# SensorModuleConector.net
KiCad netlist of a schematic drawn in EAGLE
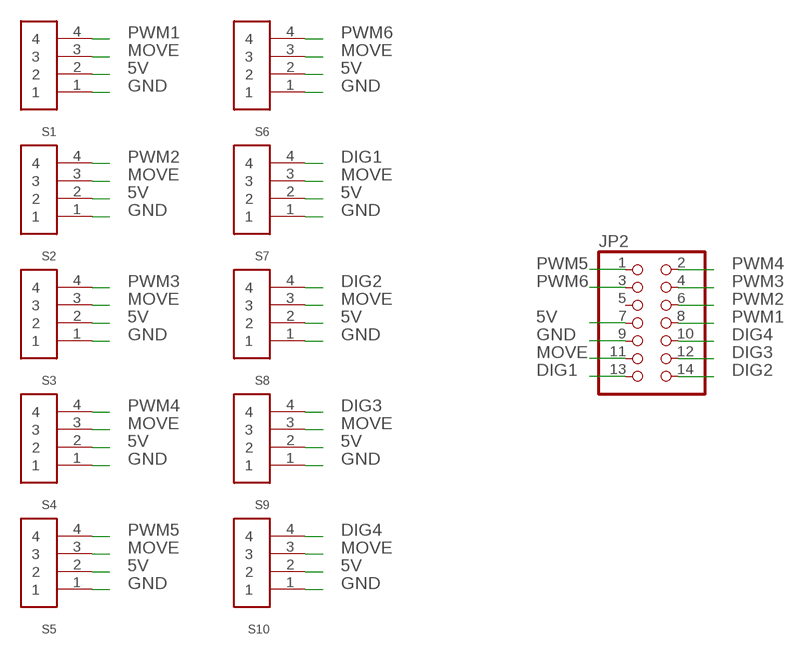
[diagram p0: schematic, sheet 1]

(export (version "E")
  (design (tool "Eeschema 10.0.6"))
  (components
    (comp (ref "JP2")
      (value "PINHD-2X7")
      (footprint "eagle-import:2X07")
      (libsource (lib "eagle-import") (part "PINHD-2X7"))
    )
    (comp (ref "S1")
      (value "CP150_1X4")
      (footprint "eagle-import:CP150_1X4")
      (libsource (lib "eagle-import") (part "CP150_1X4"))
    )
    (comp (ref "S2")
      (value "CP150_1X4")
      (footprint "eagle-import:CP150_1X4")
      (libsource (lib "eagle-import") (part "CP150_1X4"))
    )
    (comp (ref "S3")
      (value "CP150_1X4")
      (footprint "eagle-import:CP150_1X4")
      (libsource (lib "eagle-import") (part "CP150_1X4"))
    )
    (comp (ref "S4")
      (value "CP150_1X4")
      (footprint "eagle-import:CP150_1X4")
      (libsource (lib "eagle-import") (part "CP150_1X4"))
    )
    (comp (ref "S5")
      (value "CP150_1X4")
      (footprint "eagle-import:CP150_1X4")
      (libsource (lib "eagle-import") (part "CP150_1X4"))
    )
    (comp (ref "S6")
      (value "CP150_1X4")
      (footprint "eagle-import:CP150_1X4")
      (libsource (lib "eagle-import") (part "CP150_1X4"))
    )
    (comp (ref "S7")
      (value "CP150_1X4")
      (footprint "eagle-import:CP150_1X4")
      (libsource (lib "eagle-import") (part "CP150_1X4"))
    )
    (comp (ref "S8")
      (value "CP150_1X4")
      (footprint "eagle-import:CP150_1X4")
      (libsource (lib "eagle-import") (part "CP150_1X4"))
    )
    (comp (ref "S9")
      (value "CP150_1X4")
      (footprint "eagle-import:CP150_1X4")
      (libsource (lib "eagle-import") (part "CP150_1X4"))
    )
    (comp (ref "S10")
      (value "CP150_1X4")
      (footprint "eagle-import:CP150_1X4")
      (libsource (lib "eagle-import") (part "CP150_1X4"))
    )
  )
  (nets
    (net (code "1") (name "/5V") (class "Default")
      (node (ref "JP2") (pin "7") (pinfunction "7_7") (pintype "passive"))
      (node (ref "S1") (pin "2") (pinfunction "2_2") (pintype "bidirectional"))
      (node (ref "S10") (pin "2") (pinfunction "2_2") (pintype "bidirectional"))
      (node (ref "S2") (pin "2") (pinfunction "2_2") (pintype "bidirectional"))
      (node (ref "S3") (pin "2") (pinfunction "2_2") (pintype "bidirectional"))
      (node (ref "S4") (pin "2") (pinfunction "2_2") (pintype "bidirectional"))
      (node (ref "S5") (pin "2") (pinfunction "2_2") (pintype "bidirectional"))
      (node (ref "S6") (pin "2") (pinfunction "2_2") (pintype "bidirectional"))
      (node (ref "S7") (pin "2") (pinfunction "2_2") (pintype "bidirectional"))
      (node (ref "S8") (pin "2") (pinfunction "2_2") (pintype "bidirectional"))
      (node (ref "S9") (pin "2") (pinfunction "2_2") (pintype "bidirectional"))
    )
    (net (code "2") (name "/DIG1") (class "Default")
      (node (ref "JP2") (pin "13") (pinfunction "13_13") (pintype "passive"))
      (node (ref "S7") (pin "4") (pinfunction "4_4") (pintype "bidirectional"))
    )
    (net (code "3") (name "/DIG2") (class "Default")
      (node (ref "JP2") (pin "14") (pinfunction "14_14") (pintype "passive"))
      (node (ref "S8") (pin "4") (pinfunction "4_4") (pintype "bidirectional"))
    )
    (net (code "4") (name "/DIG3") (class "Default")
      (node (ref "JP2") (pin "12") (pinfunction "12_12") (pintype "passive"))
      (node (ref "S9") (pin "4") (pinfunction "4_4") (pintype "bidirectional"))
    )
    (net (code "5") (name "/DIG4") (class "Default")
      (node (ref "JP2") (pin "10") (pinfunction "10_10") (pintype "passive"))
      (node (ref "S10") (pin "4") (pinfunction "4_4") (pintype "bidirectional"))
    )
    (net (code "6") (name "/GND") (class "Default")
      (node (ref "JP2") (pin "9") (pinfunction "9_9") (pintype "passive"))
      (node (ref "S1") (pin "1") (pinfunction "1_1") (pintype "bidirectional"))
      (node (ref "S10") (pin "1") (pinfunction "1_1") (pintype "bidirectional"))
      (node (ref "S2") (pin "1") (pinfunction "1_1") (pintype "bidirectional"))
      (node (ref "S3") (pin "1") (pinfunction "1_1") (pintype "bidirectional"))
      (node (ref "S4") (pin "1") (pinfunction "1_1") (pintype "bidirectional"))
      (node (ref "S5") (pin "1") (pinfunction "1_1") (pintype "bidirectional"))
      (node (ref "S6") (pin "1") (pinfunction "1_1") (pintype "bidirectional"))
      (node (ref "S7") (pin "1") (pinfunction "1_1") (pintype "bidirectional"))
      (node (ref "S8") (pin "1") (pinfunction "1_1") (pintype "bidirectional"))
      (node (ref "S9") (pin "1") (pinfunction "1_1") (pintype "bidirectional"))
    )
    (net (code "7") (name "/MOVE") (class "Default")
      (node (ref "JP2") (pin "11") (pinfunction "11_11") (pintype "passive"))
      (node (ref "S1") (pin "3") (pinfunction "3_3") (pintype "bidirectional"))
      (node (ref "S10") (pin "3") (pinfunction "3_3") (pintype "bidirectional"))
      (node (ref "S2") (pin "3") (pinfunction "3_3") (pintype "bidirectional"))
      (node (ref "S3") (pin "3") (pinfunction "3_3") (pintype "bidirectional"))
      (node (ref "S4") (pin "3") (pinfunction "3_3") (pintype "bidirectional"))
      (node (ref "S5") (pin "3") (pinfunction "3_3") (pintype "bidirectional"))
      (node (ref "S6") (pin "3") (pinfunction "3_3") (pintype "bidirectional"))
      (node (ref "S7") (pin "3") (pinfunction "3_3") (pintype "bidirectional"))
      (node (ref "S8") (pin "3") (pinfunction "3_3") (pintype "bidirectional"))
      (node (ref "S9") (pin "3") (pinfunction "3_3") (pintype "bidirectional"))
    )
    (net (code "8") (name "/PWM1") (class "Default")
      (node (ref "JP2") (pin "8") (pinfunction "8_8") (pintype "passive"))
      (node (ref "S1") (pin "4") (pinfunction "4_4") (pintype "bidirectional"))
    )
    (net (code "9") (name "/PWM2") (class "Default")
      (node (ref "JP2") (pin "6") (pinfunction "6_6") (pintype "passive"))
      (node (ref "S2") (pin "4") (pinfunction "4_4") (pintype "bidirectional"))
    )
    (net (code "10") (name "/PWM3") (class "Default")
      (node (ref "JP2") (pin "4") (pinfunction "4_4") (pintype "passive"))
      (node (ref "S3") (pin "4") (pinfunction "4_4") (pintype "bidirectional"))
    )
    (net (code "11") (name "/PWM4") (class "Default")
      (node (ref "JP2") (pin "2") (pinfunction "2_2") (pintype "passive"))
      (node (ref "S4") (pin "4") (pinfunction "4_4") (pintype "bidirectional"))
    )
    (net (code "12") (name "/PWM5") (class "Default")
      (node (ref "JP2") (pin "1") (pinfunction "1_1") (pintype "passive"))
      (node (ref "S5") (pin "4") (pinfunction "4_4") (pintype "bidirectional"))
    )
    (net (code "13") (name "/PWM6") (class "Default")
      (node (ref "JP2") (pin "3") (pinfunction "3_3") (pintype "passive"))
      (node (ref "S6") (pin "4") (pinfunction "4_4") (pintype "bidirectional"))
    )
    (net (code "14") (name "unconnected-(JP2-Pad5)") (class "Default")
      (node (ref "JP2") (pin "5") (pinfunction "5_5") (pintype "passive"))
    )
  )
)
